# MAXstream.net
KiCad netlist of a schematic drawn in Altium Designer
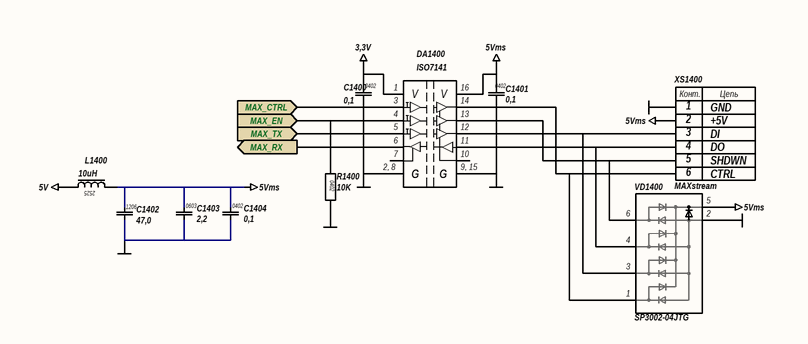
[diagram p0: MAXstream.SchDoc]

(export (version "E")
  (design (tool "Eeschema 10.0.6"))
  (components
    (comp (ref "C1400")
      (value "0,1")
      (footprint "CAP0402")
      (description "Конденсатор чип")
      (libsource (lib "EwgPassive") (part "CAP_0402"))
    )
    (comp (ref "C1401")
      (value "0,1")
      (footprint "CAP0402")
      (description "Конденсатор чип")
      (libsource (lib "EwgPassive") (part "CAP_0402"))
    )
    (comp (ref "C1402")
      (value "47,0")
      (footprint "CAP1206")
      (description "Конденсатор чип")
      (libsource (lib "EwgPassive") (part "CAP_1206"))
    )
    (comp (ref "C1403")
      (value "2,2")
      (footprint "CAP0603")
      (description "Конденсатор чип")
      (libsource (lib "EwgPassive") (part "CAP_0603"))
    )
    (comp (ref "C1404")
      (value "0,1")
      (footprint "CAP0402")
      (description "Конденсатор чип")
      (libsource (lib "EwgPassive") (part "CAP_0402"))
    )
    (comp (ref "DA1400")
      (value "ISO7141")
      (footprint "TSSOP16")
      (description "Цифровой изолятор 3 вх 1 вых")
      (libsource (lib "EwgOpto") (part "ISO7141"))
    )
    (comp (ref "L1400")
      (value "10uH")
      (footprint "IND2525")
      (description "Индуктивность чип")
      (libsource (lib "EwgPassive") (part "IND_2525"))
    )
    (comp (ref "R1400")
      (value "10K")
      (footprint "RES0402")
      (description "Резистор чип")
      (libsource (lib "EwgPassive") (part "RES_0402"))
    )
    (comp (ref "VD1400")
      (value "SP3002-04JTG")
      (footprint "SOT323-6")
      (description "Сборка диодная Шоттки 8 шт. + ESD")
      (libsource (lib "EwgActive") (part "SP3002-04JTG"))
    )
    (comp (ref "XS1400")
      (value "MAXstream")
      (footprint "MW-6M")
      (description "Разъем")
      (libsource (lib "EwgConnectors") (part "Разъем6"))
    )
  )
  (nets
    (net (code "1") (name "/MAX_CTRL") (class "Default")
      (node (ref "DA1400") (pin "3") (pinfunction "INA_3") (pintype "passive"))
    )
    (net (code "2") (name "/MAX_EN") (class "Default")
      (node (ref "DA1400") (pin "4") (pinfunction "INB_4") (pintype "passive"))
      (node (ref "R1400") (pin "1") (pintype "passive"))
    )
    (net (code "3") (name "/MAX_RX") (class "Default")
      (node (ref "DA1400") (pin "6") (pinfunction "OUTD_6") (pintype "passive"))
    )
    (net (code "4") (name "/MAX_TX") (class "Default")
      (node (ref "DA1400") (pin "5") (pinfunction "INC_5") (pintype "passive"))
    )
    (net (code "5") (name "3,3V") (class "Default")
      (node (ref "C1400") (pin "1") (pintype "passive"))
      (node (ref "DA1400") (pin "1") (pinfunction "V_1") (pintype "power_in"))
    )
    (net (code "6") (name "5V") (class "Default") (node (ref "L1400") (pin "1") (pintype "passive")))
    (net (code "7") (name "5Vms") (class "Default")
      (node (ref "C1401") (pin "1") (pintype "passive"))
      (node (ref "C1402") (pin "1") (pintype "passive"))
      (node (ref "C1403") (pin "1") (pintype "passive"))
      (node (ref "C1404") (pin "1") (pintype "passive"))
      (node (ref "DA1400") (pin "16") (pinfunction "V_16") (pintype "power_in"))
      (node (ref "L1400") (pin "2") (pintype "passive"))
      (node (ref "VD1400") (pin "5") (pintype "passive"))
      (node (ref "XS1400") (pin "2") (pinfunction "+5V_2") (pintype "passive"))
    )
    (net (code "8") (name "GND") (class "Default")
      (node (ref "C1400") (pin "2") (pintype "passive"))
      (node (ref "C1401") (pin "2") (pintype "passive"))
      (node (ref "C1402") (pin "2") (pintype "passive"))
      (node (ref "C1403") (pin "2") (pintype "passive"))
      (node (ref "C1404") (pin "2") (pintype "passive"))
      (node (ref "DA1400") (pin "15") (pinfunction "G_15") (pintype "power_in"))
      (node (ref "DA1400") (pin "2") (pinfunction "G_2") (pintype "power_in"))
      (node (ref "DA1400") (pin "8") (pinfunction "G_8") (pintype "passive"))
      (node (ref "DA1400") (pin "9") (pinfunction "G_9") (pintype "passive"))
      (node (ref "R1400") (pin "2") (pintype "passive"))
      (node (ref "VD1400") (pin "2") (pintype "passive"))
      (node (ref "XS1400") (pin "1") (pinfunction "GND_1") (pintype "passive"))
    )
    (net (code "9") (name "Net-(DA1400-IND)") (class "Default")
      (node (ref "DA1400") (pin "11") (pinfunction "IND_11") (pintype "passive"))
      (node (ref "VD1400") (pin "4") (pintype "passive"))
      (node (ref "XS1400") (pin "4") (pinfunction "DO_4") (pintype "passive"))
    )
    (net (code "10") (name "Net-(DA1400-OUTA)") (class "Default")
      (node (ref "DA1400") (pin "14") (pinfunction "OUTA_14") (pintype "passive"))
      (node (ref "VD1400") (pin "1") (pintype "passive"))
      (node (ref "XS1400") (pin "6") (pinfunction "CTRL_6") (pintype "passive"))
    )
    (net (code "11") (name "Net-(DA1400-OUTB)") (class "Default")
      (node (ref "DA1400") (pin "13") (pinfunction "OUTB_13") (pintype "passive"))
      (node (ref "VD1400") (pin "6") (pintype "passive"))
      (node (ref "XS1400") (pin "5") (pinfunction "SHDWN_5") (pintype "passive"))
    )
    (net (code "12") (name "Net-(DA1400-OUTC)") (class "Default")
      (node (ref "DA1400") (pin "12") (pinfunction "OUTC_12") (pintype "passive"))
      (node (ref "VD1400") (pin "3") (pintype "passive"))
      (node (ref "XS1400") (pin "3") (pinfunction "DI_3") (pintype "passive"))
    )
    (net (code "13") (name "unconnected-(DA1400-EN1-Pad7)") (class "Default")
      (node (ref "DA1400") (pin "7") (pinfunction "EN1_7") (pintype "passive"))
    )
    (net (code "14") (name "unconnected-(DA1400-EN2-Pad10)") (class "Default")
      (node (ref "DA1400") (pin "10") (pinfunction "EN2_10") (pintype "passive"))
    )
  )
)
